# v002.net
KiCad netlist of a schematic drawn in EAGLE
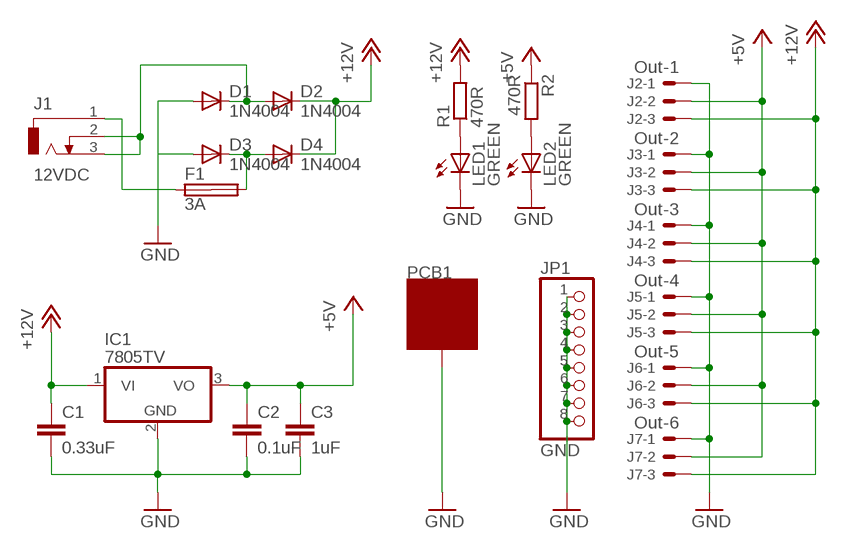
[diagram p0: schematic, sheet 1]

(export (version "E")
  (design (tool "Eeschema 10.0.6"))
  (components
    (comp (ref "C1")
      (value "0.33uF")
      (footprint "eagle-import:C050-030X075")
      (libsource (lib "eagle-import") (part "C-EU050-030X075"))
    )
    (comp (ref "C2")
      (value "0.1uF")
      (footprint "eagle-import:C050-024X044")
      (libsource (lib "eagle-import") (part "C-EU050-024X044"))
    )
    (comp (ref "C3")
      (value "1uF")
      (footprint "eagle-import:C050-045X075")
      (libsource (lib "eagle-import") (part "C-EU050-045X075"))
    )
    (comp (ref "D1")
      (value "1N4004")
      (footprint "eagle-import:DO35-7")
      (libsource (lib "eagle-import") (part "1N4148DO35-7"))
    )
    (comp (ref "D2")
      (value "1N4004")
      (footprint "eagle-import:DO35-7")
      (libsource (lib "eagle-import") (part "1N4148DO35-7"))
    )
    (comp (ref "D3")
      (value "1N4004")
      (footprint "eagle-import:DO35-7")
      (libsource (lib "eagle-import") (part "1N4148DO35-7"))
    )
    (comp (ref "D4")
      (value "1N4004")
      (footprint "eagle-import:DO35-7")
      (libsource (lib "eagle-import") (part "1N4148DO35-7"))
    )
    (comp (ref "F1")
      (value "3A")
      (footprint "eagle-import:SHK20L")
      (libsource (lib "eagle-import") (part "SHK20L"))
    )
    (comp (ref "IC1")
      (value "7805TV")
      (footprint "eagle-import:TO220V")
      (libsource (lib "eagle-import") (part "78TV05"))
    )
    (comp (ref "J1")
      (value "12VDC")
      (footprint "eagle-import:DCJ0202")
      (libsource (lib "eagle-import") (part "DCJ0202"))
    )
    (comp (ref "J2")
      (value "Out-1")
      (footprint "eagle-import:6410-03")
      (libsource (lib "eagle-import") (part "22-?-0327-2031"))
    )
    (comp (ref "J3")
      (value "Out-2")
      (footprint "eagle-import:6410-03")
      (libsource (lib "eagle-import") (part "22-?-0327-2031"))
    )
    (comp (ref "J4")
      (value "Out-3")
      (footprint "eagle-import:6410-03")
      (libsource (lib "eagle-import") (part "22-?-0327-2031"))
    )
    (comp (ref "J5")
      (value "Out-4")
      (footprint "eagle-import:6410-03")
      (libsource (lib "eagle-import") (part "22-?-0327-2031"))
    )
    (comp (ref "J6")
      (value "Out-5")
      (footprint "eagle-import:6410-03")
      (libsource (lib "eagle-import") (part "22-?-0327-2031"))
    )
    (comp (ref "J7")
      (value "Out-6")
      (footprint "eagle-import:6410-03")
      (libsource (lib "eagle-import") (part "22-?-0327-2031"))
    )
    (comp (ref "JP1")
      (value "GND")
      (footprint "eagle-import:1X08")
      (libsource (lib "eagle-import") (part "PINHD-1X8"))
    )
    (comp (ref "LED1")
      (value "GREEN")
      (footprint "eagle-import:LED3MM")
      (libsource (lib "eagle-import") (part "LED3MM"))
    )
    (comp (ref "LED2")
      (value "GREEN")
      (footprint "eagle-import:LED3MM")
      (libsource (lib "eagle-import") (part "LED3MM"))
    )
    (comp (ref "PCB1")
      (value "ZZZ_MODULE05X05")
      (footprint "eagle-import:ZZZ_MODULE_05X05")
      (libsource (lib "eagle-import") (part "ZZZ_MODULE05X05"))
    )
    (comp (ref "R1")
      (value "470R")
      (footprint "eagle-import:0204_7")
      (libsource (lib "eagle-import") (part "R-EU_0204/7"))
    )
    (comp (ref "R2")
      (value "470R")
      (footprint "eagle-import:0204_7")
      (libsource (lib "eagle-import") (part "R-EU_0204/7"))
    )
  )
  (nets
    (net (code "1") (name "+5V") (class "Default")
      (node (ref "C2") (pin "1") (pinfunction "1_1") (pintype "passive"))
      (node (ref "C3") (pin "1") (pinfunction "1_1") (pintype "passive"))
      (node (ref "IC1") (pin "3") (pinfunction "VO_3") (pintype "passive"))
      (node (ref "J2") (pin "2") (pinfunction "S_2") (pintype "passive"))
      (node (ref "J3") (pin "2") (pinfunction "S_2") (pintype "passive"))
      (node (ref "J4") (pin "2") (pinfunction "S_2") (pintype "passive"))
      (node (ref "J5") (pin "2") (pinfunction "S_2") (pintype "passive"))
      (node (ref "J6") (pin "2") (pinfunction "S_2") (pintype "passive"))
      (node (ref "J7") (pin "2") (pinfunction "S_2") (pintype "passive"))
      (node (ref "R2") (pin "1") (pinfunction "1_1") (pintype "passive"))
    )
    (net (code "2") (name "+12V") (class "Default")
      (node (ref "C1") (pin "1") (pinfunction "1_1") (pintype "passive"))
      (node (ref "D2") (pin "C") (pinfunction "C_C") (pintype "passive"))
      (node (ref "D4") (pin "C") (pinfunction "C_C") (pintype "passive"))
      (node (ref "IC1") (pin "1") (pinfunction "VI_1") (pintype "input"))
      (node (ref "J2") (pin "3") (pinfunction "S_3") (pintype "passive"))
      (node (ref "J3") (pin "3") (pinfunction "S_3") (pintype "passive"))
      (node (ref "J4") (pin "3") (pinfunction "S_3") (pintype "passive"))
      (node (ref "J5") (pin "3") (pinfunction "S_3") (pintype "passive"))
      (node (ref "J6") (pin "3") (pinfunction "S_3") (pintype "passive"))
      (node (ref "J7") (pin "3") (pinfunction "S_3") (pintype "passive"))
      (node (ref "R1") (pin "2") (pinfunction "2_2") (pintype "passive"))
    )
    (net (code "3") (name "GND") (class "Default")
      (node (ref "C1") (pin "2") (pinfunction "2_2") (pintype "passive"))
      (node (ref "C2") (pin "2") (pinfunction "2_2") (pintype "passive"))
      (node (ref "C3") (pin "2") (pinfunction "2_2") (pintype "passive"))
      (node (ref "D1") (pin "A") (pinfunction "A_A") (pintype "passive"))
      (node (ref "D3") (pin "A") (pinfunction "A_A") (pintype "passive"))
      (node (ref "IC1") (pin "2") (pinfunction "GND_2") (pintype "passive"))
      (node (ref "J2") (pin "1") (pinfunction "S_1") (pintype "passive"))
      (node (ref "J3") (pin "1") (pinfunction "S_1") (pintype "passive"))
      (node (ref "J4") (pin "1") (pinfunction "S_1") (pintype "passive"))
      (node (ref "J5") (pin "1") (pinfunction "S_1") (pintype "passive"))
      (node (ref "J6") (pin "1") (pinfunction "S_1") (pintype "passive"))
      (node (ref "J7") (pin "1") (pinfunction "S_1") (pintype "passive"))
      (node (ref "JP1") (pin "1") (pinfunction "1_1") (pintype "passive"))
      (node (ref "JP1") (pin "2") (pinfunction "2_2") (pintype "passive"))
      (node (ref "JP1") (pin "3") (pinfunction "3_3") (pintype "passive"))
      (node (ref "JP1") (pin "4") (pinfunction "4_4") (pintype "passive"))
      (node (ref "JP1") (pin "5") (pinfunction "5_5") (pintype "passive"))
      (node (ref "JP1") (pin "6") (pinfunction "6_6") (pintype "passive"))
      (node (ref "JP1") (pin "7") (pinfunction "7_7") (pintype "passive"))
      (node (ref "JP1") (pin "8") (pinfunction "8_8") (pintype "passive"))
      (node (ref "LED1") (pin "K") (pinfunction "C_K") (pintype "passive"))
      (node (ref "LED2") (pin "K") (pinfunction "C_K") (pintype "passive"))
      (node (ref "PCB1") (pin "GND@1") (pinfunction "GND_GND@1") (pintype "power_in"))
      (node (ref "PCB1") (pin "GND@2") (pinfunction "GND_GND@2") (pintype "power_in"))
      (node (ref "PCB1") (pin "GND@3") (pinfunction "GND_GND@3") (pintype "power_in"))
      (node (ref "PCB1") (pin "GND@4") (pinfunction "GND_GND@4") (pintype "power_in"))
      (node (ref "PCB1") (pin "GND@5") (pinfunction "GND_GND@5") (pintype "power_in"))
      (node (ref "PCB1") (pin "GND@6") (pinfunction "GND_GND@6") (pintype "power_in"))
      (node (ref "PCB1") (pin "GND@7") (pinfunction "GND_GND@7") (pintype "power_in"))
      (node (ref "PCB1") (pin "GND@8") (pinfunction "GND_GND@8") (pintype "power_in"))
    )
    (net (code "4") (name "Net-(D1-PadC)") (class "Default")
      (node (ref "D1") (pin "C") (pinfunction "C_C") (pintype "passive"))
      (node (ref "D2") (pin "A") (pinfunction "A_A") (pintype "passive"))
      (node (ref "J1") (pin "2") (pinfunction "2_2") (pintype "passive"))
      (node (ref "J1") (pin "3") (pinfunction "3_3") (pintype "passive"))
    )
    (net (code "5") (name "Net-(D3-PadC)") (class "Default")
      (node (ref "D3") (pin "C") (pinfunction "C_C") (pintype "passive"))
      (node (ref "D4") (pin "A") (pinfunction "A_A") (pintype "passive"))
      (node (ref "F1") (pin "2A") (pinfunction "2A_2A") (pintype "passive"))
    )
    (net (code "6") (name "Net-(F1-Pad1A)") (class "Default")
      (node (ref "F1") (pin "1A") (pinfunction "1A_1A") (pintype "passive"))
      (node (ref "J1") (pin "1") (pinfunction "1_1") (pintype "passive"))
    )
    (net (code "7") (name "Net-(LED1-PadA)") (class "Default")
      (node (ref "LED1") (pin "A") (pinfunction "A_A") (pintype "passive"))
      (node (ref "R1") (pin "1") (pinfunction "1_1") (pintype "passive"))
    )
    (net (code "8") (name "Net-(LED2-PadA)") (class "Default")
      (node (ref "LED2") (pin "A") (pinfunction "A_A") (pintype "passive"))
      (node (ref "R2") (pin "2") (pinfunction "2_2") (pintype "passive"))
    )
    (net (code "9") (name "unconnected-(F1-Pad1B)") (class "Default")
      (node (ref "F1") (pin "1B") (pinfunction "1B_1B") (pintype "passive"))
    )
    (net (code "10") (name "unconnected-(F1-Pad2B)") (class "Default")
      (node (ref "F1") (pin "2B") (pinfunction "2B_2B") (pintype "passive"))
    )
  )
)
